# CPLD.net
KiCad netlist of a schematic drawn in Altium Designer
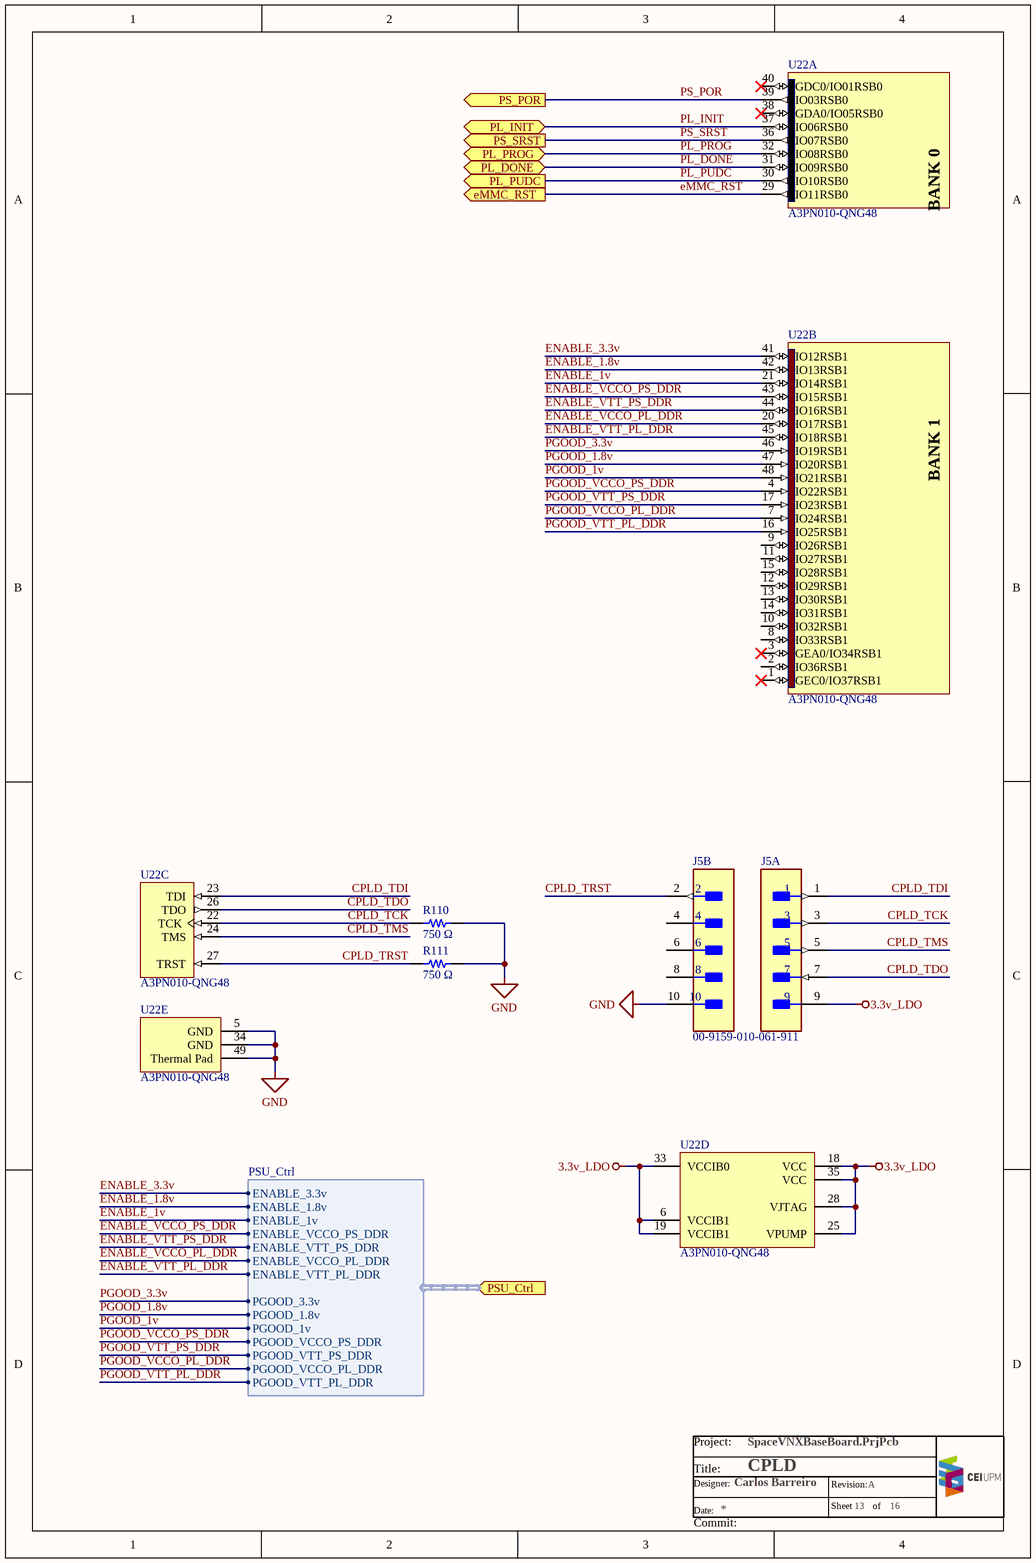
[diagram p0: CPLD.SchDoc]

(export (version "E")
  (design (tool "Eeschema 10.0.6"))
  (components
    (comp (ref "J5")
      (value "00-9159-010-061-911")
      (footprint "KYOCERA_00-9159-010-061-911")
      (description "Coplanar Open Ended Card Edge Connector 10 Pin")
      (libsource (lib "") (part "00-9159-010-061-911_1"))
    )
    (comp (ref "R110")
      (value "750 Ω")
      (footprint "PANASONIC_ERJ2G_0402")
      (description "General Purpose Thick Film Chip Resistors")
      (fields (field (name "MANUFACTURER") "Panasonic"))
      (libsource (lib "SpaceVNX") (part "ERJ2RKF7500X"))
    )
    (comp (ref "R111")
      (value "750 Ω")
      (footprint "PANASONIC_ERJ2G_0402")
      (description "General Purpose Thick Film Chip Resistors")
      (fields (field (name "MANUFACTURER") "Panasonic"))
      (libsource (lib "SpaceVNX") (part "ERJ2RKF7500X"))
    )
    (comp (ref "U22")
      (value "A3PN010-QNG48")
      (footprint "Actel_QN48")
      (libsource (lib "") (part "A3PN010-QNG48_1"))
    )
  )
  (nets
    (net (code "2") (name "/CPLD_TCK") (class "Default")
      (node (ref "J5") (pin "3") (pinfunction "3_3") (pintype "output"))
      (node (ref "R110") (pin "1") (pinfunction "1_1") (pintype "passive"))
      (node (ref "U22") (pin "22") (pinfunction "TCK_22") (pintype "input"))
    )
    (net (code "3") (name "/CPLD_TDI") (class "Default")
      (node (ref "J5") (pin "1") (pinfunction "1_1") (pintype "output"))
      (node (ref "U22") (pin "23") (pinfunction "TDI_23") (pintype "input"))
    )
    (net (code "4") (name "/CPLD_TDO") (class "Default")
      (node (ref "J5") (pin "7") (pinfunction "7_7") (pintype "input"))
      (node (ref "U22") (pin "26") (pinfunction "TDO_26") (pintype "output"))
    )
    (net (code "5") (name "/CPLD_TMS") (class "Default")
      (node (ref "J5") (pin "5") (pinfunction "5_5") (pintype "output"))
      (node (ref "U22") (pin "24") (pinfunction "TMS_24") (pintype "input"))
    )
    (net (code "6") (name "/CPLD_TRST") (class "Default")
      (node (ref "J5") (pin "2") (pinfunction "2_2") (pintype "output"))
      (node (ref "R111") (pin "1") (pinfunction "1_1") (pintype "passive"))
      (node (ref "U22") (pin "27") (pinfunction "TRST_27") (pintype "input"))
    )
    (net (code "7") (name "/ENABLE_1.8v") (class "Default")
      (node (ref "U22") (pin "42") (pinfunction "IO13RSB1_42") (pintype "bidirectional"))
    )
    (net (code "8") (name "/ENABLE_1v") (class "Default")
      (node (ref "U22") (pin "21") (pinfunction "IO14RSB1_21") (pintype "bidirectional"))
    )
    (net (code "9") (name "/ENABLE_3.3v") (class "Default")
      (node (ref "U22") (pin "41") (pinfunction "IO12RSB1_41") (pintype "bidirectional"))
    )
    (net (code "10") (name "/ENABLE_VCCO_PL_DDR") (class "Default")
      (node (ref "U22") (pin "20") (pinfunction "IO17RSB1_20") (pintype "bidirectional"))
    )
    (net (code "11") (name "/ENABLE_VCCO_PS_DDR") (class "Default")
      (node (ref "U22") (pin "43") (pinfunction "IO15RSB1_43") (pintype "bidirectional"))
    )
    (net (code "12") (name "/ENABLE_VTT_PL_DDR") (class "Default")
      (node (ref "U22") (pin "45") (pinfunction "IO18RSB1_45") (pintype "bidirectional"))
    )
    (net (code "13") (name "/ENABLE_VTT_PS_DDR") (class "Default")
      (node (ref "U22") (pin "44") (pinfunction "IO16RSB1_44") (pintype "bidirectional"))
    )
    (net (code "14") (name "/PGOOD_1.8v") (class "Default")
      (node (ref "U22") (pin "47") (pinfunction "IO20RSB1_47") (pintype "bidirectional"))
    )
    (net (code "15") (name "/PGOOD_1v") (class "Default")
      (node (ref "U22") (pin "48") (pinfunction "IO21RSB1_48") (pintype "bidirectional"))
    )
    (net (code "16") (name "/PGOOD_3.3v") (class "Default")
      (node (ref "U22") (pin "46") (pinfunction "IO19RSB1_46") (pintype "bidirectional"))
    )
    (net (code "17") (name "/PGOOD_VCCO_PL_DDR") (class "Default")
      (node (ref "U22") (pin "7") (pinfunction "IO24RSB1_7") (pintype "bidirectional"))
    )
    (net (code "18") (name "/PGOOD_VCCO_PS_DDR") (class "Default")
      (node (ref "U22") (pin "4") (pinfunction "IO22RSB1_4") (pintype "bidirectional"))
    )
    (net (code "19") (name "/PGOOD_VTT_PL_DDR") (class "Default")
      (node (ref "U22") (pin "16") (pinfunction "IO25RSB1_16") (pintype "bidirectional"))
    )
    (net (code "20") (name "/PGOOD_VTT_PS_DDR") (class "Default")
      (node (ref "U22") (pin "17") (pinfunction "IO23RSB1_17") (pintype "bidirectional"))
    )
    (net (code "21") (name "/PL_DONE") (class "Default")
      (node (ref "U22") (pin "31") (pinfunction "IO09RSB0_31") (pintype "bidirectional"))
    )
    (net (code "22") (name "/PL_INIT") (class "Default")
      (node (ref "U22") (pin "37") (pinfunction "IO06RSB0_37") (pintype "bidirectional"))
    )
    (net (code "23") (name "/PL_PROG") (class "Default")
      (node (ref "U22") (pin "32") (pinfunction "IO08RSB0_32") (pintype "bidirectional"))
    )
    (net (code "24") (name "/PL_PUDC") (class "Default")
      (node (ref "U22") (pin "30") (pinfunction "IO10RSB0_30") (pintype "bidirectional"))
    )
    (net (code "25") (name "/PS_POR") (class "Default")
      (node (ref "U22") (pin "39") (pinfunction "IO03RSB0_39") (pintype "bidirectional"))
    )
    (net (code "26") (name "/PS_SRST") (class "Default")
      (node (ref "U22") (pin "36") (pinfunction "IO07RSB0_36") (pintype "bidirectional"))
    )
    (net (code "27") (name "/eMMC_RST") (class "Default")
      (node (ref "U22") (pin "29") (pinfunction "IO11RSB0_29") (pintype "bidirectional"))
    )
    (net (code "29") (name "3.3v_LDO") (class "Default")
      (node (ref "J5") (pin "9") (pinfunction "9_9") (pintype "power_in"))
      (node (ref "U22") (pin "18") (pinfunction "VCC_18") (pintype "power_in"))
      (node (ref "U22") (pin "19") (pinfunction "VCCIB1_19") (pintype "power_in"))
      (node (ref "U22") (pin "25") (pinfunction "VPUMP_25") (pintype "power_in"))
      (node (ref "U22") (pin "28") (pinfunction "VJTAG_28") (pintype "power_in"))
      (node (ref "U22") (pin "33") (pinfunction "VCCIB0_33") (pintype "power_in"))
      (node (ref "U22") (pin "35") (pinfunction "VCC_35") (pintype "power_in"))
      (node (ref "U22") (pin "6") (pinfunction "VCCIB1_6") (pintype "power_in"))
    )
    (net (code "30") (name "GND") (class "Default")
      (node (ref "J5") (pin "10") (pinfunction "10_10") (pintype "passive"))
      (node (ref "R110") (pin "2") (pinfunction "2_2") (pintype "passive"))
      (node (ref "R111") (pin "2") (pinfunction "2_2") (pintype "passive"))
      (node (ref "U22") (pin "34") (pinfunction "GND_34") (pintype "power_in"))
      (node (ref "U22") (pin "49") (pinfunction "Thermal_Pad_49") (pintype "power_in"))
      (node (ref "U22") (pin "5") (pinfunction "GND_5") (pintype "power_in"))
    )
    (net (code "31") (name "unconnected-(J5-Pad4)") (class "Default")
      (node (ref "J5") (pin "4") (pinfunction "4_4") (pintype "passive"))
    )
    (net (code "32") (name "unconnected-(J5-Pad6)") (class "Default")
      (node (ref "J5") (pin "6") (pinfunction "6_6") (pintype "passive"))
    )
    (net (code "33") (name "unconnected-(J5-Pad8)") (class "Default")
      (node (ref "J5") (pin "8") (pinfunction "8_8") (pintype "passive"))
    )
    (net (code "34") (name "unconnected-(U22A-GDA0{slash}IO05RSB0-Pad38)") (class "Default")
      (node (ref "U22") (pin "38") (pinfunction "GDA0/IO05RSB0_38") (pintype "bidirectional+no_connect"))
    )
    (net (code "35") (name "unconnected-(U22A-GDC0{slash}IO01RSB0-Pad40)") (class "Default")
      (node (ref "U22") (pin "40") (pinfunction "GDC0/IO01RSB0_40") (pintype "bidirectional+no_connect"))
    )
    (net (code "36") (name "unconnected-(U22B-GEA0{slash}IO34RSB1-Pad3)") (class "Default")
      (node (ref "U22") (pin "3") (pinfunction "GEA0/IO34RSB1_3") (pintype "bidirectional+no_connect"))
    )
    (net (code "37") (name "unconnected-(U22B-GEC0{slash}IO37RSB1-Pad1)") (class "Default")
      (node (ref "U22") (pin "1") (pinfunction "GEC0/IO37RSB1_1") (pintype "bidirectional+no_connect"))
    )
    (net (code "38") (name "unconnected-(U22B-IO26RSB1-Pad9)") (class "Default")
      (node (ref "U22") (pin "9") (pinfunction "IO26RSB1_9") (pintype "bidirectional"))
    )
    (net (code "39") (name "unconnected-(U22B-IO27RSB1-Pad11)") (class "Default")
      (node (ref "U22") (pin "11") (pinfunction "IO27RSB1_11") (pintype "bidirectional"))
    )
    (net (code "40") (name "unconnected-(U22B-IO28RSB1-Pad15)") (class "Default")
      (node (ref "U22") (pin "15") (pinfunction "IO28RSB1_15") (pintype "bidirectional"))
    )
    (net (code "41") (name "unconnected-(U22B-IO29RSB1-Pad12)") (class "Default")
      (node (ref "U22") (pin "12") (pinfunction "IO29RSB1_12") (pintype "bidirectional"))
    )
    (net (code "42") (name "unconnected-(U22B-IO30RSB1-Pad13)") (class "Default")
      (node (ref "U22") (pin "13") (pinfunction "IO30RSB1_13") (pintype "bidirectional"))
    )
    (net (code "43") (name "unconnected-(U22B-IO31RSB1-Pad14)") (class "Default")
      (node (ref "U22") (pin "14") (pinfunction "IO31RSB1_14") (pintype "bidirectional"))
    )
    (net (code "44") (name "unconnected-(U22B-IO32RSB1-Pad10)") (class "Default")
      (node (ref "U22") (pin "10") (pinfunction "IO32RSB1_10") (pintype "bidirectional"))
    )
    (net (code "45") (name "unconnected-(U22B-IO33RSB1-Pad8)") (class "Default")
      (node (ref "U22") (pin "8") (pinfunction "IO33RSB1_8") (pintype "bidirectional"))
    )
    (net (code "46") (name "unconnected-(U22B-IO36RSB1-Pad2)") (class "Default")
      (node (ref "U22") (pin "2") (pinfunction "IO36RSB1_2") (pintype "bidirectional"))
    )
  )
)
